# Plipbox.net
KiCad netlist of a schematic drawn in EAGLE
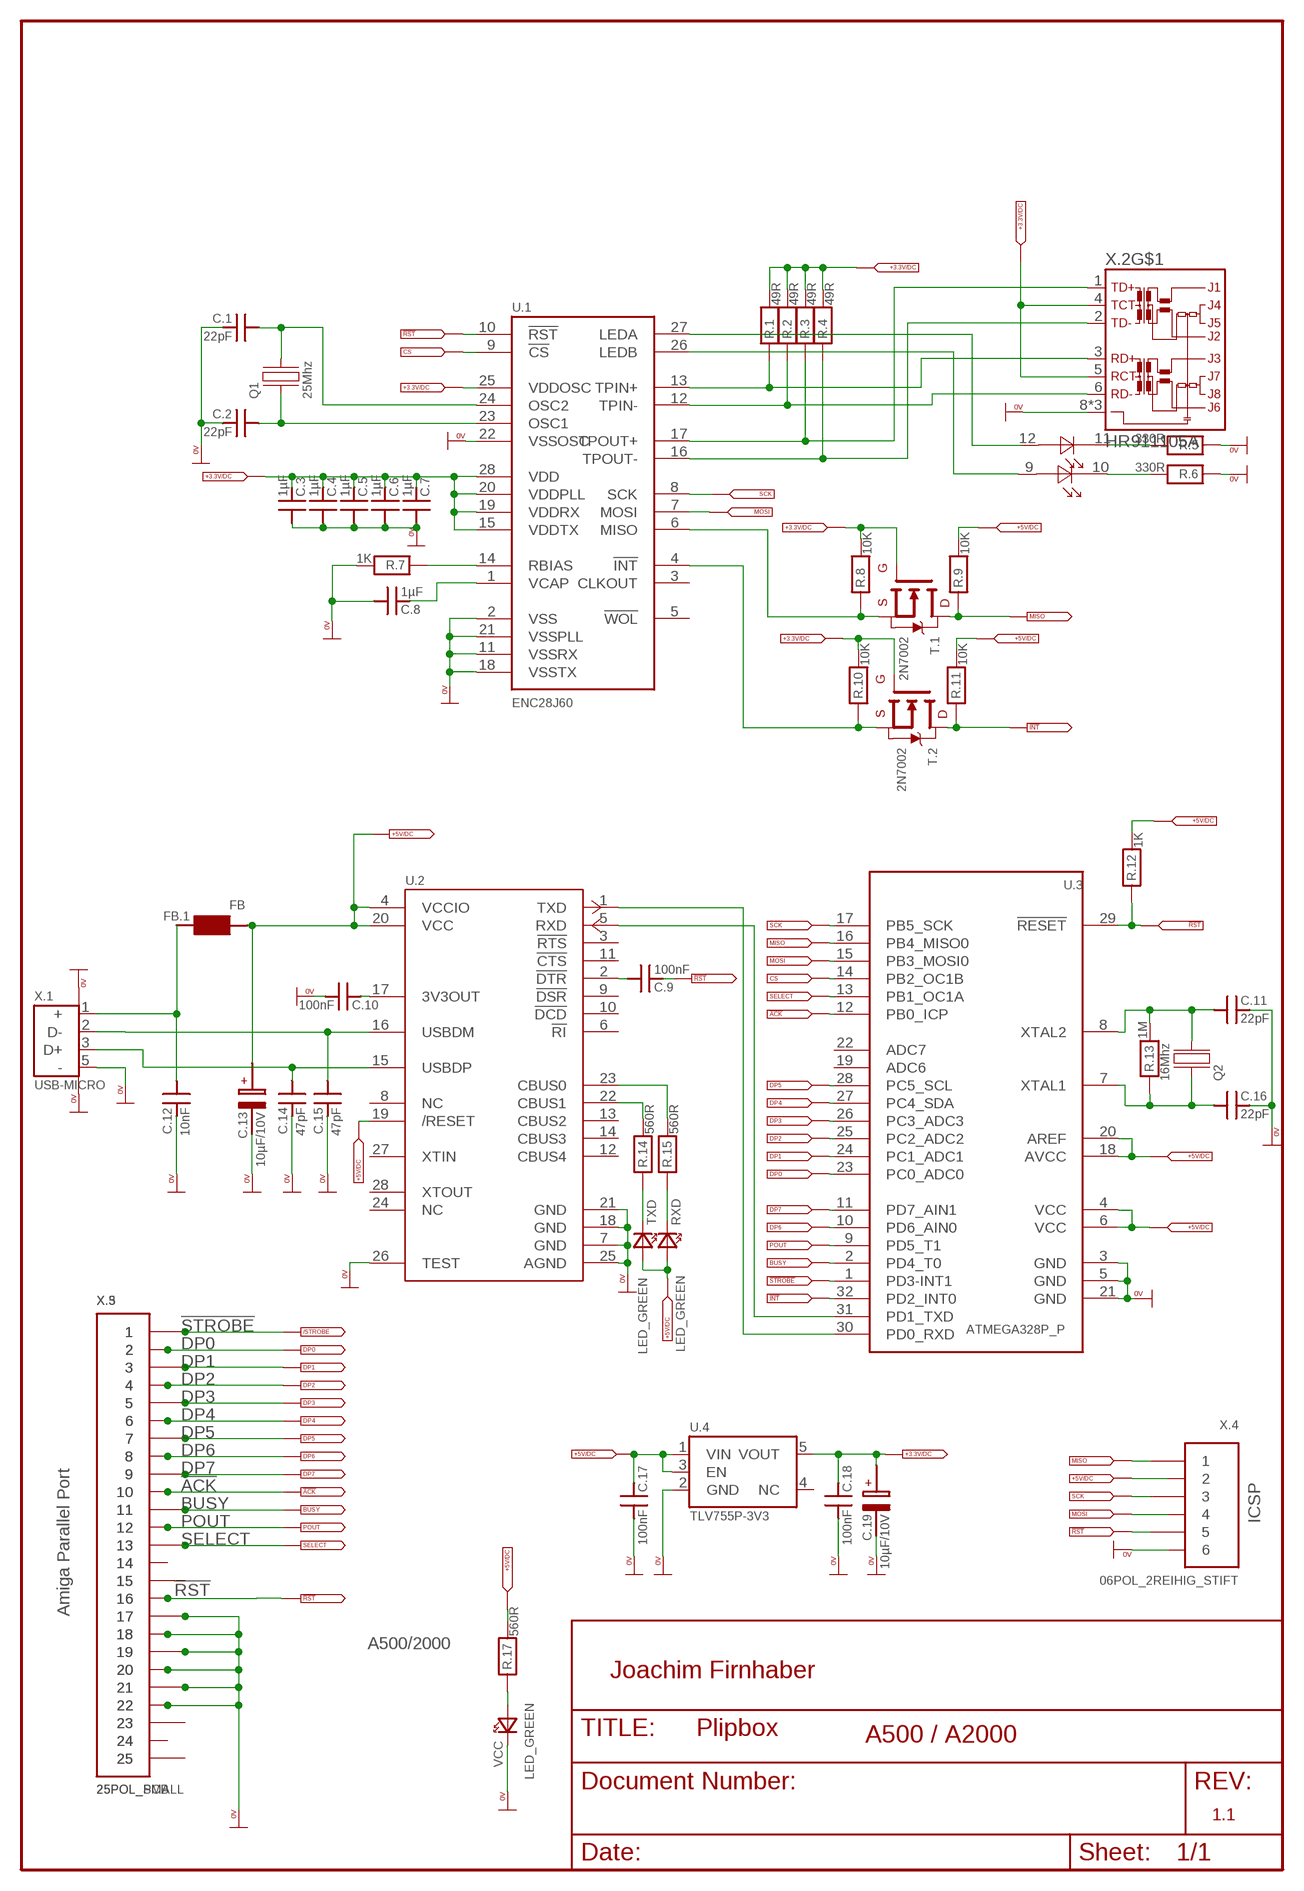
[diagram p0: schematic, sheet 1]

(export (version "E")
  (design (tool "Eeschema 10.0.6"))
  (components
    (comp (ref "C.1")
      (value "22pF")
      (footprint "eagle-import:0805")
      (libsource (lib "eagle-import") (part "CAPACITOR_SMD_0805"))
    )
    (comp (ref "C.2")
      (value "22pF")
      (footprint "eagle-import:0805")
      (libsource (lib "eagle-import") (part "CAPACITOR_SMD_0805"))
    )
    (comp (ref "C.3")
      (value "1µF")
      (footprint "eagle-import:0805")
      (libsource (lib "eagle-import") (part "CAPACITOR_SMD_0805"))
    )
    (comp (ref "C.4")
      (value "1µF")
      (footprint "eagle-import:0805")
      (libsource (lib "eagle-import") (part "CAPACITOR_SMD_0805"))
    )
    (comp (ref "C.5")
      (value "1µF")
      (footprint "eagle-import:0805")
      (libsource (lib "eagle-import") (part "CAPACITOR_SMD_0805"))
    )
    (comp (ref "C.6")
      (value "1µF")
      (footprint "eagle-import:0805")
      (libsource (lib "eagle-import") (part "CAPACITOR_SMD_0805"))
    )
    (comp (ref "C.7")
      (value "1µF")
      (footprint "eagle-import:0805")
      (libsource (lib "eagle-import") (part "CAPACITOR_SMD_0805"))
    )
    (comp (ref "C.8")
      (value "1µF")
      (footprint "eagle-import:0805")
      (libsource (lib "eagle-import") (part "CAPACITOR_SMD_0805"))
    )
    (comp (ref "C.9")
      (value "100nF")
      (footprint "eagle-import:0805")
      (libsource (lib "eagle-import") (part "CAPACITOR_SMD_0805"))
    )
    (comp (ref "C.10")
      (value "100nF")
      (footprint "eagle-import:0805")
      (libsource (lib "eagle-import") (part "CAPACITOR_SMD_0805"))
    )
    (comp (ref "C.11")
      (value "22pF")
      (footprint "eagle-import:0805")
      (libsource (lib "eagle-import") (part "CAPACITOR_SMD_0805"))
    )
    (comp (ref "C.12")
      (value "10nF")
      (footprint "eagle-import:0805")
      (libsource (lib "eagle-import") (part "CAPACITOR_SMD_0805"))
    )
    (comp (ref "C.13")
      (value "10µF/10V")
      (footprint "eagle-import:3216")
      (libsource (lib "eagle-import") (part "TANTAL_SMD_A(3216)"))
    )
    (comp (ref "C.14")
      (value "47pF")
      (footprint "eagle-import:0805")
      (libsource (lib "eagle-import") (part "CAPACITOR_SMD_0805"))
    )
    (comp (ref "C.15")
      (value "47pF")
      (footprint "eagle-import:0805")
      (libsource (lib "eagle-import") (part "CAPACITOR_SMD_0805"))
    )
    (comp (ref "C.16")
      (value "22pF")
      (footprint "eagle-import:0805")
      (libsource (lib "eagle-import") (part "CAPACITOR_SMD_0805"))
    )
    (comp (ref "C.17")
      (value "100nF")
      (footprint "eagle-import:0805")
      (libsource (lib "eagle-import") (part "CAPACITOR_SMD_0805"))
    )
    (comp (ref "C.18")
      (value "100nF")
      (footprint "eagle-import:0805")
      (libsource (lib "eagle-import") (part "CAPACITOR_SMD_0805"))
    )
    (comp (ref "C.19")
      (value "10µF/10V")
      (footprint "eagle-import:3216")
      (libsource (lib "eagle-import") (part "TANTAL_SMD_A(3216)"))
    )
    (comp (ref "FB.1")
      (value "FB")
      (footprint "eagle-import:0805")
      (libsource (lib "eagle-import") (part "FERRIT-BEAD"))
    )
    (comp (ref "Q1")
      (value "25Mhz")
      (footprint "eagle-import:3,4X2,7X0,75")
      (libsource (lib "eagle-import") (part "QUARZ_3,4X2,7"))
    )
    (comp (ref "Q2")
      (value "16Mhz")
      (footprint "eagle-import:3,4X2,7X0,75")
      (libsource (lib "eagle-import") (part "QUARZ_3,4X2,7"))
    )
    (comp (ref "R.1")
      (value "49R")
      (footprint "eagle-import:0805")
      (libsource (lib "eagle-import") (part "RESISTOR_SMD_0805"))
    )
    (comp (ref "R.2")
      (value "49R")
      (footprint "eagle-import:0805")
      (libsource (lib "eagle-import") (part "RESISTOR_SMD_0805"))
    )
    (comp (ref "R.3")
      (value "49R")
      (footprint "eagle-import:0805")
      (libsource (lib "eagle-import") (part "RESISTOR_SMD_0805"))
    )
    (comp (ref "R.4")
      (value "49R")
      (footprint "eagle-import:0805")
      (libsource (lib "eagle-import") (part "RESISTOR_SMD_0805"))
    )
    (comp (ref "R.5")
      (value "330R")
      (footprint "eagle-import:0805")
      (libsource (lib "eagle-import") (part "RESISTOR_SMD_0805"))
    )
    (comp (ref "R.6")
      (value "330R")
      (footprint "eagle-import:0805")
      (libsource (lib "eagle-import") (part "RESISTOR_SMD_0805"))
    )
    (comp (ref "R.7")
      (value "1K")
      (footprint "eagle-import:0805")
      (libsource (lib "eagle-import") (part "RESISTOR_SMD_0805"))
    )
    (comp (ref "R.8")
      (value "10K")
      (footprint "eagle-import:0805")
      (libsource (lib "eagle-import") (part "RESISTOR_SMD_0805"))
    )
    (comp (ref "R.9")
      (value "10K")
      (footprint "eagle-import:0805")
      (libsource (lib "eagle-import") (part "RESISTOR_SMD_0805"))
    )
    (comp (ref "R.10")
      (value "10K")
      (footprint "eagle-import:0805")
      (libsource (lib "eagle-import") (part "RESISTOR_SMD_0805"))
    )
    (comp (ref "R.11")
      (value "10K")
      (footprint "eagle-import:0805")
      (libsource (lib "eagle-import") (part "RESISTOR_SMD_0805"))
    )
    (comp (ref "R.12")
      (value "1K")
      (footprint "eagle-import:0805")
      (libsource (lib "eagle-import") (part "RESISTOR_SMD_0805"))
    )
    (comp (ref "R.13")
      (value "1M")
      (footprint "eagle-import:0805")
      (libsource (lib "eagle-import") (part "RESISTOR_SMD_0805"))
    )
    (comp (ref "R.14")
      (value "560R")
      (footprint "eagle-import:0805")
      (libsource (lib "eagle-import") (part "RESISTOR_SMD_0805"))
    )
    (comp (ref "R.15")
      (value "560R")
      (footprint "eagle-import:0805")
      (libsource (lib "eagle-import") (part "RESISTOR_SMD_0805"))
    )
    (comp (ref "R.17")
      (value "560R")
      (footprint "eagle-import:0805")
      (libsource (lib "eagle-import") (part "RESISTOR_SMD_0805"))
    )
    (comp (ref "RXD")
      (value "LED_GREEN")
      (footprint "eagle-import:0805")
      (libsource (lib "eagle-import") (part "LED_0805"))
    )
    (comp (ref "T.1")
      (value "2N7002")
      (footprint "eagle-import:SOT23")
      (libsource (lib "eagle-import") (part "2N7002_N"))
    )
    (comp (ref "T.2")
      (value "2N7002")
      (footprint "eagle-import:SOT23")
      (libsource (lib "eagle-import") (part "2N7002_N"))
    )
    (comp (ref "TXD")
      (value "LED_GREEN")
      (footprint "eagle-import:0805")
      (libsource (lib "eagle-import") (part "LED_0805"))
    )
    (comp (ref "U.1")
      (value "ENC28J60")
      (footprint "eagle-import:SSOP28")
      (libsource (lib "eagle-import") (part "EN28J60"))
    )
    (comp (ref "U.2")
      (value "FT232R_FT232RL")
      (footprint "eagle-import:SSOP28")
      (libsource (lib "eagle-import") (part "FT232R_FT232RL"))
    )
    (comp (ref "U.3")
      (value "ATMEGA328P_P")
      (footprint "eagle-import:LQFP32")
      (libsource (lib "eagle-import") (part "ATMEGA328P_P"))
    )
    (comp (ref "U.4")
      (value "TLV755P-3V3")
      (footprint "eagle-import:SOT23-5")
      (libsource (lib "eagle-import") (part "TLV755P"))
    )
    (comp (ref "VCC")
      (value "LED_GREEN")
      (footprint "eagle-import:0805")
      (libsource (lib "eagle-import") (part "LED_0805"))
    )
    (comp (ref "X.1")
      (value "USB-MICRO")
      (footprint "eagle-import:USB_MICRO")
      (libsource (lib "eagle-import") (part "USB-MICRO"))
    )
    (comp (ref "X.2")
      (value "HR911105A")
      (footprint "eagle-import:HR911105A")
      (libsource (lib "eagle-import") (part "HR911105A"))
    )
    (comp (ref "X.3")
      (value "25POL_SMALL")
      (footprint "eagle-import:SUB-D_25_M_ONLY")
      (libsource (lib "eagle-import") (part "25POL_SMALL"))
    )
    (comp (ref "X.4")
      (value "06POL_2REIHIG_STIFT")
      (footprint "eagle-import:STIFT_2_03")
      (libsource (lib "eagle-import") (part "06POL_2REIHIG_STIFT"))
    )
    (comp (ref "X.5")
      (value "25POL_PCB")
      (footprint "eagle-import:SUB-D_25M_L")
      (libsource (lib "eagle-import") (part "25POL_PCB"))
    )
  )
  (nets
    (net (code "1") (name "!ACK") (class "Default")
      (node (ref "U.3") (pin "12") (pinfunction "PB0_ICP_12") (pintype "bidirectional"))
      (node (ref "X.3") (pin "10") (pinfunction "10_10") (pintype "passive"))
      (node (ref "X.5") (pin "10") (pinfunction "10_10") (pintype "passive"))
    )
    (net (code "2") (name "!INT") (class "Default")
      (node (ref "R.11") (pin "1") (pinfunction "1_1") (pintype "passive"))
      (node (ref "T.2") (pin "3") (pinfunction "DRAIN_3") (pintype "passive"))
      (node (ref "U.3") (pin "32") (pinfunction "PD2_INT0_32") (pintype "bidirectional"))
    )
    (net (code "3") (name "!RST") (class "Default")
      (node (ref "C.9") (pin "2") (pinfunction "2_2") (pintype "passive"))
      (node (ref "R.12") (pin "1") (pinfunction "1_1") (pintype "passive"))
      (node (ref "U.1") (pin "10") (pinfunction "~{RST}_10") (pintype "bidirectional"))
      (node (ref "U.3") (pin "29") (pinfunction "~{RESET}_29") (pintype "bidirectional"))
      (node (ref "X.3") (pin "16") (pinfunction "16_16") (pintype "passive"))
      (node (ref "X.4") (pin "5") (pinfunction "5_5") (pintype "passive"))
      (node (ref "X.5") (pin "16") (pinfunction "16_16") (pintype "passive"))
    )
    (net (code "4") (name "!STROBE") (class "Default")
      (node (ref "U.3") (pin "1") (pinfunction "PD3-INT1_1") (pintype "bidirectional"))
      (node (ref "X.3") (pin "1") (pinfunction "1_1") (pintype "passive"))
      (node (ref "X.5") (pin "1") (pinfunction "1_1") (pintype "passive"))
    )
    (net (code "5") (name "+3.3V-IN") (class "Default")
      (node (ref "C.18") (pin "2") (pinfunction "2_2") (pintype "passive"))
      (node (ref "C.19") (pin "+") (pinfunction "+_+") (pintype "passive"))
      (node (ref "C.3") (pin "2") (pinfunction "2_2") (pintype "passive"))
      (node (ref "C.4") (pin "2") (pinfunction "2_2") (pintype "passive"))
      (node (ref "C.5") (pin "2") (pinfunction "2_2") (pintype "passive"))
      (node (ref "C.6") (pin "2") (pinfunction "2_2") (pintype "passive"))
      (node (ref "C.7") (pin "2") (pinfunction "2_2") (pintype "passive"))
      (node (ref "R.1") (pin "2") (pinfunction "2_2") (pintype "passive"))
      (node (ref "R.10") (pin "2") (pinfunction "2_2") (pintype "passive"))
      (node (ref "R.2") (pin "2") (pinfunction "2_2") (pintype "passive"))
      (node (ref "R.3") (pin "2") (pinfunction "2_2") (pintype "passive"))
      (node (ref "R.4") (pin "2") (pinfunction "2_2") (pintype "passive"))
      (node (ref "R.8") (pin "2") (pinfunction "2_2") (pintype "passive"))
      (node (ref "T.1") (pin "1") (pinfunction "GATE_1") (pintype "passive"))
      (node (ref "T.2") (pin "1") (pinfunction "GATE_1") (pintype "passive"))
      (node (ref "U.1") (pin "15") (pinfunction "VDDTX_15") (pintype "bidirectional"))
      (node (ref "U.1") (pin "19") (pinfunction "VDDRX_19") (pintype "bidirectional"))
      (node (ref "U.1") (pin "20") (pinfunction "VDDPLL_20") (pintype "bidirectional"))
      (node (ref "U.1") (pin "25") (pinfunction "VDDOSC_25") (pintype "bidirectional"))
      (node (ref "U.1") (pin "28") (pinfunction "VDD_28") (pintype "bidirectional"))
      (node (ref "U.4") (pin "5") (pinfunction "VOUT_5") (pintype "bidirectional"))
      (node (ref "X.2") (pin "4") (pinfunction "TCT-_4") (pintype "passive"))
      (node (ref "X.2") (pin "5") (pinfunction "RCT-_5") (pintype "passive"))
    )
    (net (code "6") (name "+5V-IN") (class "Default")
      (node (ref "C.13") (pin "+") (pinfunction "+_+") (pintype "passive"))
      (node (ref "C.17") (pin "2") (pinfunction "2_2") (pintype "passive"))
      (node (ref "FB.1") (pin "1") (pinfunction "1_1") (pintype "passive"))
      (node (ref "R.11") (pin "2") (pinfunction "2_2") (pintype "passive"))
      (node (ref "R.12") (pin "2") (pinfunction "2_2") (pintype "passive"))
      (node (ref "R.17") (pin "2") (pinfunction "2_2") (pintype "passive"))
      (node (ref "R.9") (pin "2") (pinfunction "2_2") (pintype "passive"))
      (node (ref "RXD") (pin "A") (pinfunction "ANODE_A") (pintype "passive"))
      (node (ref "TXD") (pin "A") (pinfunction "ANODE_A") (pintype "passive"))
      (node (ref "U.2") (pin "19") (pinfunction "/RESET_19") (pintype "bidirectional"))
      (node (ref "U.2") (pin "20") (pinfunction "VCC_20") (pintype "bidirectional"))
      (node (ref "U.2") (pin "4") (pinfunction "VCCIO_4") (pintype "bidirectional"))
      (node (ref "U.3") (pin "18") (pinfunction "AVCC_18") (pintype "bidirectional"))
      (node (ref "U.3") (pin "20") (pinfunction "AREF_20") (pintype "bidirectional"))
      (node (ref "U.3") (pin "4") (pinfunction "VCC_4") (pintype "bidirectional"))
      (node (ref "U.3") (pin "6") (pinfunction "VCC_6") (pintype "bidirectional"))
      (node (ref "U.4") (pin "1") (pinfunction "VIN_1") (pintype "bidirectional"))
      (node (ref "U.4") (pin "3") (pinfunction "EN_3") (pintype "bidirectional"))
      (node (ref "X.4") (pin "2") (pinfunction "2_2") (pintype "passive"))
    )
    (net (code "7") (name "0V") (class "Default")
      (node (ref "C.1") (pin "2") (pinfunction "2_2") (pintype "passive"))
      (node (ref "C.10") (pin "1") (pinfunction "1_1") (pintype "passive"))
      (node (ref "C.11") (pin "2") (pinfunction "2_2") (pintype "passive"))
      (node (ref "C.12") (pin "2") (pinfunction "2_2") (pintype "passive"))
      (node (ref "C.13") (pin "-") (pinfunction "-_-") (pintype "passive"))
      (node (ref "C.14") (pin "2") (pinfunction "2_2") (pintype "passive"))
      (node (ref "C.15") (pin "2") (pinfunction "2_2") (pintype "passive"))
      (node (ref "C.16") (pin "2") (pinfunction "2_2") (pintype "passive"))
      (node (ref "C.17") (pin "1") (pinfunction "1_1") (pintype "passive"))
      (node (ref "C.18") (pin "1") (pinfunction "1_1") (pintype "passive"))
      (node (ref "C.19") (pin "-") (pinfunction "-_-") (pintype "passive"))
      (node (ref "C.2") (pin "2") (pinfunction "2_2") (pintype "passive"))
      (node (ref "C.3") (pin "1") (pinfunction "1_1") (pintype "passive"))
      (node (ref "C.4") (pin "1") (pinfunction "1_1") (pintype "passive"))
      (node (ref "C.5") (pin "1") (pinfunction "1_1") (pintype "passive"))
      (node (ref "C.6") (pin "1") (pinfunction "1_1") (pintype "passive"))
      (node (ref "C.7") (pin "1") (pinfunction "1_1") (pintype "passive"))
      (node (ref "C.8") (pin "1") (pinfunction "1_1") (pintype "passive"))
      (node (ref "R.5") (pin "1") (pinfunction "1_1") (pintype "passive"))
      (node (ref "R.6") (pin "1") (pinfunction "1_1") (pintype "passive"))
      (node (ref "R.7") (pin "2") (pinfunction "2_2") (pintype "passive"))
      (node (ref "U.1") (pin "11") (pinfunction "VSSRX_11") (pintype "bidirectional"))
      (node (ref "U.1") (pin "18") (pinfunction "VSSTX_18") (pintype "bidirectional"))
      (node (ref "U.1") (pin "2") (pinfunction "VSS_2") (pintype "bidirectional"))
      (node (ref "U.1") (pin "21") (pinfunction "VSSPLL_21") (pintype "bidirectional"))
      (node (ref "U.1") (pin "22") (pinfunction "VSSOSC_22") (pintype "bidirectional"))
      (node (ref "U.2") (pin "18") (pinfunction "GND_18") (pintype "bidirectional"))
      (node (ref "U.2") (pin "21") (pinfunction "GND_21") (pintype "bidirectional"))
      (node (ref "U.2") (pin "25") (pinfunction "AGND_25") (pintype "bidirectional"))
      (node (ref "U.2") (pin "26") (pinfunction "TEST_26") (pintype "bidirectional"))
      (node (ref "U.2") (pin "7") (pinfunction "GND_7") (pintype "bidirectional"))
      (node (ref "U.3") (pin "21") (pinfunction "GND_21") (pintype "bidirectional"))
      (node (ref "U.3") (pin "3") (pinfunction "GND_3") (pintype "bidirectional"))
      (node (ref "U.3") (pin "5") (pinfunction "GND_5") (pintype "bidirectional"))
      (node (ref "U.4") (pin "2") (pinfunction "GND_2") (pintype "bidirectional"))
      (node (ref "VCC") (pin "K") (pinfunction "KATHODE_K") (pintype "passive"))
      (node (ref "X.1") (pin "5") (pinfunction "-_5") (pintype "bidirectional"))
      (node (ref "X.1") (pin "6") (pinfunction "GND_6") (pintype "bidirectional"))
      (node (ref "X.1") (pin "7") (pinfunction "GND_7") (pintype "bidirectional"))
      (node (ref "X.2") (pin "8") (pinfunction "GND_8") (pintype "passive"))
      (node (ref "X.2") (pin "Z1") (pinfunction "GND_Z1") (pintype "passive"))
      (node (ref "X.2") (pin "Z2") (pinfunction "GND_Z2") (pintype "passive"))
      (node (ref "X.3") (pin "17") (pinfunction "17_17") (pintype "passive"))
      (node (ref "X.3") (pin "18") (pinfunction "18_18") (pintype "passive"))
      (node (ref "X.3") (pin "19") (pinfunction "19_19") (pintype "passive"))
      (node (ref "X.3") (pin "20") (pinfunction "20_20") (pintype "passive"))
      (node (ref "X.3") (pin "21") (pinfunction "21_21") (pintype "passive"))
      (node (ref "X.3") (pin "22") (pinfunction "22_22") (pintype "passive"))
      (node (ref "X.4") (pin "6") (pinfunction "6_6") (pintype "passive"))
      (node (ref "X.5") (pin "17") (pinfunction "17_17") (pintype "passive"))
      (node (ref "X.5") (pin "18") (pinfunction "18_18") (pintype "passive"))
      (node (ref "X.5") (pin "19") (pinfunction "19_19") (pintype "passive"))
      (node (ref "X.5") (pin "20") (pinfunction "20_20") (pintype "passive"))
      (node (ref "X.5") (pin "21") (pinfunction "21_21") (pintype "passive"))
      (node (ref "X.5") (pin "22") (pinfunction "22_22") (pintype "passive"))
    )
    (net (code "8") (name "BUSY") (class "Default")
      (node (ref "U.3") (pin "2") (pinfunction "PD4_T0_2") (pintype "bidirectional"))
      (node (ref "X.3") (pin "11") (pinfunction "11_11") (pintype "passive"))
      (node (ref "X.5") (pin "11") (pinfunction "11_11") (pintype "passive"))
    )
    (net (code "9") (name "CS") (class "Default")
      (node (ref "U.1") (pin "9") (pinfunction "~{CS}_9") (pintype "bidirectional"))
      (node (ref "U.3") (pin "14") (pinfunction "PB2_OC1B_14") (pintype "bidirectional"))
    )
    (net (code "10") (name "DP0") (class "Default")
      (node (ref "U.3") (pin "23") (pinfunction "PC0_ADC0_23") (pintype "bidirectional"))
      (node (ref "X.3") (pin "2") (pinfunction "2_2") (pintype "passive"))
      (node (ref "X.5") (pin "2") (pinfunction "2_2") (pintype "passive"))
    )
    (net (code "11") (name "DP1") (class "Default")
      (node (ref "U.3") (pin "24") (pinfunction "PC1_ADC1_24") (pintype "bidirectional"))
      (node (ref "X.3") (pin "3") (pinfunction "3_3") (pintype "passive"))
      (node (ref "X.5") (pin "3") (pinfunction "3_3") (pintype "passive"))
    )
    (net (code "12") (name "DP2") (class "Default")
      (node (ref "U.3") (pin "25") (pinfunction "PC2_ADC2_25") (pintype "bidirectional"))
      (node (ref "X.3") (pin "4") (pinfunction "4_4") (pintype "passive"))
      (node (ref "X.5") (pin "4") (pinfunction "4_4") (pintype "passive"))
    )
    (net (code "13") (name "DP3") (class "Default")
      (node (ref "U.3") (pin "26") (pinfunction "PC3_ADC3_26") (pintype "bidirectional"))
      (node (ref "X.3") (pin "5") (pinfunction "5_5") (pintype "passive"))
      (node (ref "X.5") (pin "5") (pinfunction "5_5") (pintype "passive"))
    )
    (net (code "14") (name "DP4") (class "Default")
      (node (ref "U.3") (pin "27") (pinfunction "PC4_SDA_27") (pintype "bidirectional"))
      (node (ref "X.3") (pin "6") (pinfunction "6_6") (pintype "passive"))
      (node (ref "X.5") (pin "6") (pinfunction "6_6") (pintype "passive"))
    )
    (net (code "15") (name "DP5") (class "Default")
      (node (ref "U.3") (pin "28") (pinfunction "PC5_SCL_28") (pintype "bidirectional"))
      (node (ref "X.3") (pin "7") (pinfunction "7_7") (pintype "passive"))
      (node (ref "X.5") (pin "7") (pinfunction "7_7") (pintype "passive"))
    )
    (net (code "16") (name "DP6") (class "Default")
      (node (ref "U.3") (pin "10") (pinfunction "PD6_AIN0_10") (pintype "bidirectional"))
      (node (ref "X.3") (pin "8") (pinfunction "8_8") (pintype "passive"))
      (node (ref "X.5") (pin "8") (pinfunction "8_8") (pintype "passive"))
    )
    (net (code "17") (name "DP7") (class "Default")
      (node (ref "U.3") (pin "11") (pinfunction "PD7_AIN1_11") (pintype "bidirectional"))
      (node (ref "X.3") (pin "9") (pinfunction "9_9") (pintype "passive"))
      (node (ref "X.5") (pin "9") (pinfunction "9_9") (pintype "passive"))
    )
    (net (code "18") (name "MISO") (class "Default")
      (node (ref "R.9") (pin "1") (pinfunction "1_1") (pintype "passive"))
      (node (ref "T.1") (pin "3") (pinfunction "DRAIN_3") (pintype "passive"))
      (node (ref "U.3") (pin "16") (pinfunction "PB4_MISO0_16") (pintype "bidirectional"))
      (node (ref "X.4") (pin "1") (pinfunction "1_1") (pintype "passive"))
    )
    (net (code "19") (name "MOSI") (class "Default")
      (node (ref "U.1") (pin "7") (pinfunction "MOSI_7") (pintype "bidirectional"))
      (node (ref "U.3") (pin "15") (pinfunction "PB3_MOSI0_15") (pintype "bidirectional"))
      (node (ref "X.4") (pin "4") (pinfunction "4_4") (pintype "passive"))
    )
    (net (code "20") (name "Net-(Q1-XTAL1)") (class "Default")
      (node (ref "C.2") (pin "1") (pinfunction "1_1") (pintype "passive"))
      (node (ref "Q1") (pin "2") (pinfunction "XTAL1_2") (pintype "bidirectional"))
      (node (ref "U.1") (pin "23") (pinfunction "OSC1_23") (pintype "bidirectional"))
    )
    (net (code "21") (name "Net-(Q1-XTAL2)") (class "Default")
      (node (ref "C.1") (pin "1") (pinfunction "1_1") (pintype "passive"))
      (node (ref "Q1") (pin "4") (pinfunction "XTAL2_4") (pintype "bidirectional"))
      (node (ref "U.1") (pin "24") (pinfunction "OSC2_24") (pintype "bidirectional"))
    )
    (net (code "22") (name "Net-(Q2-XTAL1)") (class "Default")
      (node (ref "C.16") (pin "1") (pinfunction "1_1") (pintype "passive"))
      (node (ref "Q2") (pin "2") (pinfunction "XTAL1_2") (pintype "bidirectional"))
      (node (ref "R.13") (pin "1") (pinfunction "1_1") (pintype "passive"))
      (node (ref "U.3") (pin "7") (pinfunction "XTAL1_7") (pintype "bidirectional"))
    )
    (net (code "23") (name "Net-(Q2-XTAL2)") (class "Default")
      (node (ref "C.11") (pin "1") (pinfunction "1_1") (pintype "passive"))
      (node (ref "Q2") (pin "4") (pinfunction "XTAL2_4") (pintype "bidirectional"))
      (node (ref "R.13") (pin "2") (pinfunction "2_2") (pintype "passive"))
      (node (ref "U.3") (pin "8") (pinfunction "XTAL2_8") (pintype "bidirectional"))
    )
    (net (code "24") (name "Net-(RXD-KATHODE)") (class "Default")
      (node (ref "R.15") (pin "1") (pinfunction "1_1") (pintype "passive"))
      (node (ref "RXD") (pin "K") (pinfunction "KATHODE_K") (pintype "passive"))
    )
    (net (code "25") (name "Net-(T.1-SOURCE)") (class "Default")
      (node (ref "R.8") (pin "1") (pinfunction "1_1") (pintype "passive"))
      (node (ref "T.1") (pin "2") (pinfunction "SOURCE_2") (pintype "passive"))
      (node (ref "U.1") (pin "6") (pinfunction "MISO_6") (pintype "bidirectional"))
    )
    (net (code "26") (name "Net-(T.2-SOURCE)") (class "Default")
      (node (ref "R.10") (pin "1") (pinfunction "1_1") (pintype "passive"))
      (node (ref "T.2") (pin "2") (pinfunction "SOURCE_2") (pintype "passive"))
      (node (ref "U.1") (pin "4") (pinfunction "~{INT}_4") (pintype "bidirectional"))
    )
    (net (code "27") (name "Net-(TXD-KATHODE)") (class "Default")
      (node (ref "R.14") (pin "1") (pinfunction "1_1") (pintype "passive"))
      (node (ref "TXD") (pin "K") (pinfunction "KATHODE_K") (pintype "passive"))
    )
    (net (code "28") (name "Net-(U.1-LEDA)") (class "Default")
      (node (ref "U.1") (pin "27") (pinfunction "LEDA_27") (pintype "bidirectional"))
      (node (ref "X.2") (pin "12") (pinfunction "A_12") (pintype "bidirectional"))
    )
    (net (code "29") (name "Net-(U.1-LEDB)") (class "Default")
      (node (ref "U.1") (pin "26") (pinfunction "LEDB_26") (pintype "bidirectional"))
      (node (ref "X.2") (pin "9") (pinfunction "A_9") (pintype "bidirectional"))
    )
    (net (code "30") (name "Net-(U.1-RBIAS)") (class "Default")
      (node (ref "R.7") (pin "1") (pinfunction "1_1") (pintype "passive"))
      (node (ref "U.1") (pin "14") (pinfunction "RBIAS_14") (pintype "bidirectional"))
    )
    (net (code "31") (name "Net-(U.1-TPIN+)") (class "Default")
      (node (ref "R.1") (pin "1") (pinfunction "1_1") (pintype "passive"))
      (node (ref "U.1") (pin "13") (pinfunction "TPIN+_13") (pintype "bidirectional"))
      (node (ref "X.2") (pin "3") (pinfunction "RD+_3") (pintype "passive"))
    )
    (net (code "32") (name "Net-(U.1-TPIN-)") (class "Default")
      (node (ref "R.2") (pin "1") (pinfunction "1_1") (pintype "passive"))
      (node (ref "U.1") (pin "12") (pinfunction "TPIN-_12") (pintype "bidirectional"))
      (node (ref "X.2") (pin "6") (pinfunction "RD-_6") (pintype "passive"))
    )
    (net (code "33") (name "Net-(U.1-TPOUT+)") (class "Default")
      (node (ref "R.3") (pin "1") (pinfunction "1_1") (pintype "passive"))
      (node (ref "U.1") (pin "17") (pinfunction "TPOUT+_17") (pintype "bidirectional"))
      (node (ref "X.2") (pin "1") (pinfunction "TD+_1") (pintype "passive"))
    )
    (net (code "34") (name "Net-(U.1-TPOUT-)") (class "Default")
      (node (ref "R.4") (pin "1") (pinfunction "1_1") (pintype "passive"))
      (node (ref "U.1") (pin "16") (pinfunction "TPOUT-_16") (pintype "bidirectional"))
      (node (ref "X.2") (pin "2") (pinfunction "TD-_2") (pintype "passive"))
    )
    (net (code "35") (name "Net-(U.1-VCAP)") (class "Default")
      (node (ref "C.8") (pin "2") (pinfunction "2_2") (pintype "passive"))
      (node (ref "U.1") (pin "1") (pinfunction "VCAP_1") (pintype "bidirectional"))
    )
    (net (code "36") (name "Net-(U.2-3V3OUT)") (class "Default")
      (node (ref "C.10") (pin "2") (pinfunction "2_2") (pintype "passive"))
      (node (ref "U.2") (pin "17") (pinfunction "3V3OUT_17") (pintype "bidirectional"))
    )
    (net (code "37") (name "Net-(U.2-CBUS0)") (class "Default")
      (node (ref "R.15") (pin "2") (pinfunction "2_2") (pintype "passive"))
      (node (ref "U.2") (pin "23") (pinfunction "CBUS0_23") (pintype "bidirectional"))
    )
    (net (code "38") (name "Net-(U.2-CBUS1)") (class "Default")
      (node (ref "R.14") (pin "2") (pinfunction "2_2") (pintype "passive"))
      (node (ref "U.2") (pin "22") (pinfunction "CBUS1_22") (pintype "bidirectional"))
    )
    (net (code "39") (name "Net-(U.2-RXD)") (class "Default")
      (node (ref "U.2") (pin "5") (pinfunction "RXD_5") (pintype "bidirectional"))
      (node (ref "U.3") (pin "31") (pinfunction "PD1_TXD_31") (pintype "bidirectional"))
    )
    (net (code "40") (name "Net-(U.2-TXD)") (class "Default")
      (node (ref "U.2") (pin "1") (pinfunction "TXD_1") (pintype "bidirectional"))
      (node (ref "U.3") (pin "30") (pinfunction "PD0_RXD_30") (pintype "bidirectional"))
    )
    (net (code "41") (name "Net-(U.2-USBDM)") (class "Default")
      (node (ref "C.15") (pin "1") (pinfunction "1_1") (pintype "passive"))
      (node (ref "U.2") (pin "16") (pinfunction "USBDM_16") (pintype "bidirectional"))
      (node (ref "X.1") (pin "2") (pinfunction "D-_2") (pintype "bidirectional"))
    )
    (net (code "42") (name "Net-(U.2-USBDP)") (class "Default")
      (node (ref "C.14") (pin "1") (pinfunction "1_1") (pintype "passive"))
      (node (ref "U.2") (pin "15") (pinfunction "USBDP_15") (pintype "bidirectional"))
      (node (ref "X.1") (pin "3") (pinfunction "D+_3") (pintype "bidirectional"))
    )
    (net (code "43") (name "Net-(U.2-~{DTR})") (class "Default")
      (node (ref "C.9") (pin "1") (pinfunction "1_1") (pintype "passive"))
      (node (ref "U.2") (pin "2") (pinfunction "~{DTR}_2") (pintype "bidirectional"))
    )
    (net (code "44") (name "Net-(VCC-ANODE)") (class "Default")
      (node (ref "R.17") (pin "1") (pinfunction "1_1") (pintype "passive"))
      (node (ref "VCC") (pin "A") (pinfunction "ANODE_A") (pintype "passive"))
    )
    (net (code "45") (name "Net-(X.1-+)") (class "Default")
      (node (ref "C.12") (pin "1") (pinfunction "1_1") (pintype "passive"))
      (node (ref "FB.1") (pin "2") (pinfunction "2_2") (pintype "passive"))
      (node (ref "X.1") (pin "1") (pinfunction "+_1") (pintype "bidirectional"))
    )
    (net (code "46") (name "Net-(X.2B-K)") (class "Default")
      (node (ref "R.5") (pin "2") (pinfunction "2_2") (pintype "passive"))
      (node (ref "X.2") (pin "11") (pinfunction "K_11") (pintype "bidirectional"))
    )
    (net (code "47") (name "Net-(X.2C-K)") (class "Default")
      (node (ref "R.6") (pin "2") (pinfunction "2_2") (pintype "passive"))
      (node (ref "X.2") (pin "10") (pinfunction "K_10") (pintype "bidirectional"))
    )
    (net (code "48") (name "Net-(X.3-Pad14)") (class "Default")
      (node (ref "X.3") (pin "14") (pinfunction "14_14") (pintype "passive"))
      (node (ref "X.5") (pin "14") (pinfunction "14_14") (pintype "passive"))
    )
    (net (code "49") (name "Net-(X.3-Pad15)") (class "Default")
      (node (ref "X.3") (pin "15") (pinfunction "15_15") (pintype "passive"))
      (node (ref "X.5") (pin "15") (pinfunction "15_15") (pintype "passive"))
    )
    (net (code "50") (name "Net-(X.3-Pad23)") (class "Default")
      (node (ref "X.3") (pin "23") (pinfunction "23_23") (pintype "passive"))
      (node (ref "X.5") (pin "23") (pinfunction "23_23") (pintype "passive"))
    )
    (net (code "51") (name "Net-(X.3-Pad24)") (class "Default")
      (node (ref "X.3") (pin "24") (pinfunction "24_24") (pintype "passive"))
      (node (ref "X.5") (pin "24") (pinfunction "24_24") (pintype "passive"))
    )
    (net (code "52") (name "Net-(X.3-Pad25)") (class "Default")
      (node (ref "X.3") (pin "25") (pinfunction "25_25") (pintype "passive"))
      (node (ref "X.5") (pin "25") (pinfunction "25_25") (pintype "passive"))
    )
    (net (code "53") (name "POUT") (class "Default")
      (node (ref "U.3") (pin "9") (pinfunction "PD5_T1_9") (pintype "bidirectional"))
      (node (ref "X.3") (pin "12") (pinfunction "12_12") (pintype "passive"))
      (node (ref "X.5") (pin "12") (pinfunction "12_12") (pintype "passive"))
    )
    (net (code "54") (name "SCK") (class "Default")
      (node (ref "U.1") (pin "8") (pinfunction "SCK_8") (pintype "bidirectional"))
      (node (ref "U.3") (pin "17") (pinfunction "PB5_SCK_17") (pintype "bidirectional"))
      (node (ref "X.4") (pin "3") (pinfunction "3_3") (pintype "passive"))
    )
    (net (code "55") (name "SELECT") (class "Default")
      (node (ref "U.3") (pin "13") (pinfunction "PB1_OC1A_13") (pintype "bidirectional"))
      (node (ref "X.3") (pin "13") (pinfunction "13_13") (pintype "passive"))
      (node (ref "X.5") (pin "13") (pinfunction "13_13") (pintype "passive"))
    )
    (net (code "56") (name "unconnected-(U.1-CLKOUT-Pad3)") (class "Default")
      (node (ref "U.1") (pin "3") (pinfunction "CLKOUT_3") (pintype "bidirectional"))
    )
    (net (code "57") (name "unconnected-(U.1-~{WOL}-Pad5)") (class "Default")
      (node (ref "U.1") (pin "5") (pinfunction "~{WOL}_5") (pintype "bidirectional"))
    )
    (net (code "58") (name "unconnected-(U.2-CBUS2-Pad13)") (class "Default")
      (node (ref "U.2") (pin "13") (pinfunction "CBUS2_13") (pintype "bidirectional"))
    )
    (net (code "59") (name "unconnected-(U.2-CBUS3-Pad14)") (class "Default")
      (node (ref "U.2") (pin "14") (pinfunction "CBUS3_14") (pintype "bidirectional"))
    )
    (net (code "60") (name "unconnected-(U.2-CBUS4-Pad12)") (class "Default")
      (node (ref "U.2") (pin "12") (pinfunction "CBUS4_12") (pintype "bidirectional"))
    )
    (net (code "61") (name "unconnected-(U.2-NC-Pad8)") (class "Default")
      (node (ref "U.2") (pin "8") (pinfunction "NC_8") (pintype "bidirectional"))
    )
    (net (code "62") (name "unconnected-(U.2-NC-Pad24)") (class "Default")
      (node (ref "U.2") (pin "24") (pinfunction "NC_24") (pintype "bidirectional"))
    )
    (net (code "63") (name "unconnected-(U.2-XTIN-Pad27)") (class "Default")
      (node (ref "U.2") (pin "27") (pinfunction "XTIN_27") (pintype "bidirectional"))
    )
    (net (code "64") (name "unconnected-(U.2-XTOUT-Pad28)") (class "Default")
      (node (ref "U.2") (pin "28") (pinfunction "XTOUT_28") (pintype "bidirectional"))
    )
    (net (code "65") (name "unconnected-(U.2-~{CTS}-Pad11)") (class "Default")
      (node (ref "U.2") (pin "11") (pinfunction "~{CTS}_11") (pintype "bidirectional"))
    )
    (net (code "66") (name "unconnected-(U.2-~{DCD}-Pad10)") (class "Default")
      (node (ref "U.2") (pin "10") (pinfunction "~{DCD}_10") (pintype "bidirectional"))
    )
    (net (code "67") (name "unconnected-(U.2-~{DSR}-Pad9)") (class "Default")
      (node (ref "U.2") (pin "9") (pinfunction "~{DSR}_9") (pintype "bidirectional"))
    )
    (net (code "68") (name "unconnected-(U.2-~{RI}-Pad6)") (class "Default")
      (node (ref "U.2") (pin "6") (pinfunction "~{RI}_6") (pintype "bidirectional"))
    )
    (net (code "69") (name "unconnected-(U.2-~{RTS}-Pad3)") (class "Default")
      (node (ref "U.2") (pin "3") (pinfunction "~{RTS}_3") (pintype "bidirectional"))
    )
    (net (code "70") (name "unconnected-(U.3-ADC6-Pad19)") (class "Default")
      (node (ref "U.3") (pin "19") (pinfunction "ADC6_19") (pintype "bidirectional"))
    )
    (net (code "71") (name "unconnected-(U.3-ADC7-Pad22)") (class "Default")
      (node (ref "U.3") (pin "22") (pinfunction "ADC7_22") (pintype "bidirectional"))
    )
    (net (code "72") (name "unconnected-(U.4-NC-Pad4)") (class "Default")
      (node (ref "U.4") (pin "4") (pinfunction "NC_4") (pintype "bidirectional"))
    )
  )
)
